# usb_shield.net
KiCad netlist of a schematic drawn in EAGLE
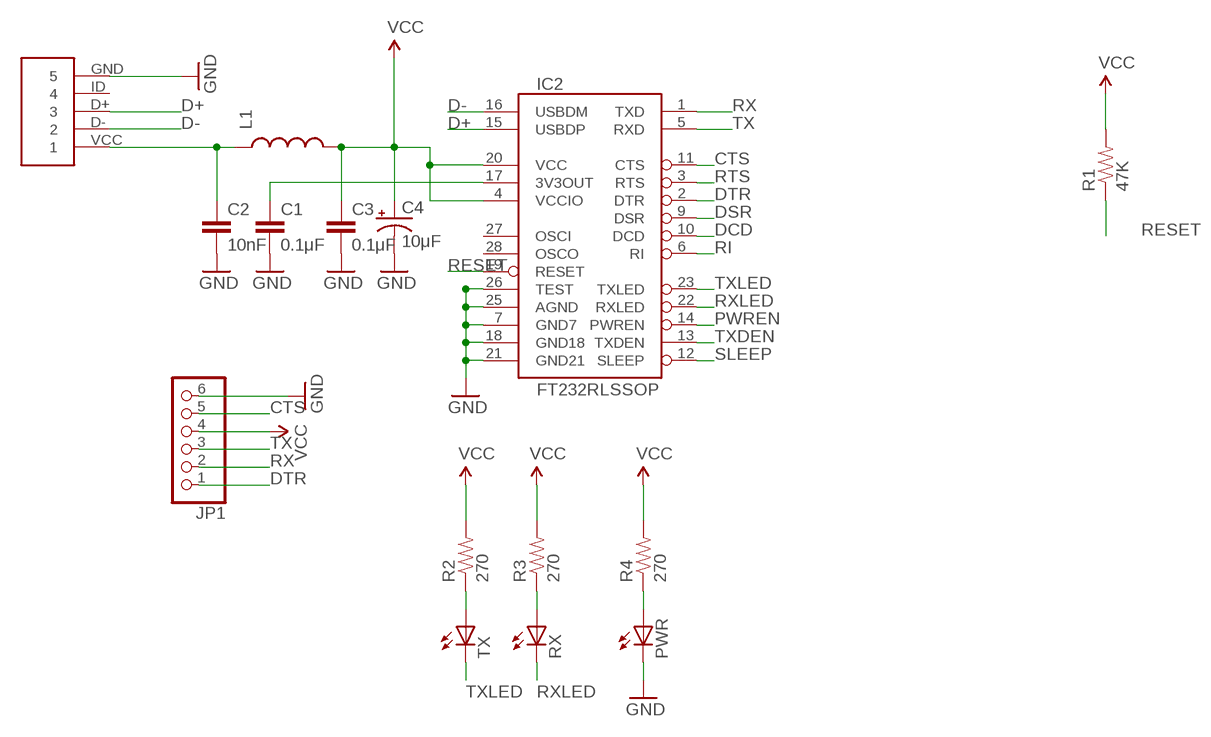
[diagram p0: schematic, sheet 1]

(export (version "E")
  (design (tool "Eeschema 10.0.6"))
  (components
    (comp (ref "C1")
      (value "0.1μF")
      (footprint "eagle-import:0603-CAP")
      (libsource (lib "eagle-import") (part "CAP0603-CAP"))
    )
    (comp (ref "C2")
      (value "10nF")
      (footprint "eagle-import:0603-CAP")
      (libsource (lib "eagle-import") (part "CAP0603-CAP"))
    )
    (comp (ref "C3")
      (value "0.1μF")
      (footprint "eagle-import:0603-CAP")
      (libsource (lib "eagle-import") (part "CAP0603-CAP"))
    )
    (comp (ref "C4")
      (value "10μF")
      (footprint "eagle-import:EIA3216")
      (libsource (lib "eagle-import") (part "CAP_POL1206"))
    )
    (comp (ref "IC2")
      (value "FT232RLSSOP")
      (footprint "eagle-import:SSOP28DB")
      (libsource (lib "eagle-import") (part "FT232RLSSOP"))
    )
    (comp (ref "JP1")
      (value "PINHD-1X6")
      (footprint "eagle-import:1X06")
      (libsource (lib "eagle-import") (part "PINHD-1X6"))
    )
    (comp (ref "L1")
      (value "INDUCTOR0603")
      (footprint "eagle-import:0603")
      (libsource (lib "eagle-import") (part "INDUCTOR0603"))
    )
    (comp (ref "PWR")
      (value "LEDCHIP-LED0805")
      (footprint "eagle-import:CHIP-LED0805")
      (libsource (lib "eagle-import") (part "LEDCHIP-LED0805"))
    )
    (comp (ref "R1")
      (value "47K")
      (footprint "eagle-import:0603-RES")
      (libsource (lib "eagle-import") (part "RESISTOR0603-RES"))
    )
    (comp (ref "R2")
      (value "270")
      (footprint "eagle-import:0603-RES")
      (libsource (lib "eagle-import") (part "RESISTOR0603-RES"))
    )
    (comp (ref "R3")
      (value "270")
      (footprint "eagle-import:0603-RES")
      (libsource (lib "eagle-import") (part "RESISTOR0603-RES"))
    )
    (comp (ref "R4")
      (value "270")
      (footprint "eagle-import:0603-RES")
      (libsource (lib "eagle-import") (part "RESISTOR0603-RES"))
    )
    (comp (ref "RX")
      (value "LEDCHIP-LED0805")
      (footprint "eagle-import:CHIP-LED0805")
      (libsource (lib "eagle-import") (part "LEDCHIP-LED0805"))
    )
    (comp (ref "TX")
      (value "LEDCHIP-LED0805")
      (footprint "eagle-import:CHIP-LED0805")
      (libsource (lib "eagle-import") (part "LEDCHIP-LED0805"))
    )
    (comp (ref "U$1")
      (value "USB-MICRO-B-FEMALE")
      (footprint "eagle-import:USB-MICRO-B-FEMALE")
      (libsource (lib "eagle-import") (part "USB-MICRO-B-FEMALE"))
    )
  )
  (nets
    (net (code "1") (name "/CTS") (class "Default")
      (node (ref "IC2") (pin "11") (pinfunction "CTS_11") (pintype "input"))
      (node (ref "JP1") (pin "5") (pinfunction "5_5") (pintype "passive"))
    )
    (net (code "2") (name "/D+") (class "Default")
      (node (ref "IC2") (pin "15") (pinfunction "USBDP_15") (pintype "bidirectional"))
      (node (ref "U$1") (pin "D+") (pinfunction "3_D+") (pintype "bidirectional"))
    )
    (net (code "3") (name "/D-") (class "Default")
      (node (ref "IC2") (pin "16") (pinfunction "USBDM_16") (pintype "bidirectional"))
      (node (ref "U$1") (pin "D-") (pinfunction "2_D-") (pintype "bidirectional"))
    )
    (net (code "4") (name "/DCD") (class "Default")
      (node (ref "IC2") (pin "10") (pinfunction "DCD_10") (pintype "input"))
    )
    (net (code "5") (name "/DSR") (class "Default")
      (node (ref "IC2") (pin "9") (pinfunction "DSR_9") (pintype "input"))
    )
    (net (code "6") (name "/DTR") (class "Default")
      (node (ref "IC2") (pin "2") (pinfunction "DTR_2") (pintype "output"))
      (node (ref "JP1") (pin "1") (pinfunction "1_1") (pintype "passive"))
    )
    (net (code "7") (name "/PWREN") (class "Default")
      (node (ref "IC2") (pin "14") (pinfunction "PWREN_14") (pintype "input"))
    )
    (net (code "8") (name "/RESET") (class "Default")
      (node (ref "IC2") (pin "19") (pinfunction "RESET_19") (pintype "input"))
      (node (ref "R1") (pin "1") (pinfunction "1_1") (pintype "passive"))
    )
    (net (code "9") (name "/RI") (class "Default")
      (node (ref "IC2") (pin "6") (pinfunction "RI_6") (pintype "input"))
    )
    (net (code "10") (name "/RTS") (class "Default")
      (node (ref "IC2") (pin "3") (pinfunction "RTS_3") (pintype "output"))
    )
    (net (code "11") (name "/RX") (class "Default")
      (node (ref "IC2") (pin "1") (pinfunction "TXD_1") (pintype "output"))
      (node (ref "JP1") (pin "2") (pinfunction "2_2") (pintype "passive"))
    )
    (net (code "12") (name "/RXLED") (class "Default")
      (node (ref "IC2") (pin "22") (pinfunction "RXLED_22") (pintype "input"))
      (node (ref "RX") (pin "C") (pinfunction "C_C") (pintype "passive"))
    )
    (net (code "13") (name "/SLEEP") (class "Default")
      (node (ref "IC2") (pin "12") (pinfunction "SLEEP_12") (pintype "input"))
    )
    (net (code "14") (name "/TX") (class "Default")
      (node (ref "IC2") (pin "5") (pinfunction "RXD_5") (pintype "input"))
      (node (ref "JP1") (pin "3") (pinfunction "3_3") (pintype "passive"))
    )
    (net (code "15") (name "/TXDEN") (class "Default")
      (node (ref "IC2") (pin "13") (pinfunction "TXDEN_13") (pintype "input"))
    )
    (net (code "16") (name "/TXLED") (class "Default")
      (node (ref "IC2") (pin "23") (pinfunction "TXLED_23") (pintype "input"))
      (node (ref "TX") (pin "C") (pinfunction "C_C") (pintype "passive"))
    )
    (net (code "17") (name "GND") (class "Default")
      (node (ref "C1") (pin "2") (pinfunction "2_2") (pintype "passive"))
      (node (ref "C2") (pin "2") (pinfunction "2_2") (pintype "passive"))
      (node (ref "C3") (pin "2") (pinfunction "2_2") (pintype "passive"))
      (node (ref "C4") (pin "C") (pinfunction "-_C") (pintype "passive"))
      (node (ref "IC2") (pin "18") (pinfunction "GND18_18") (pintype "power_in"))
      (node (ref "IC2") (pin "21") (pinfunction "GND21_21") (pintype "power_in"))
      (node (ref "IC2") (pin "25") (pinfunction "AGND_25") (pintype "power_in"))
      (node (ref "IC2") (pin "26") (pinfunction "TEST_26") (pintype "input"))
      (node (ref "IC2") (pin "7") (pinfunction "GND7_7") (pintype "power_in"))
      (node (ref "JP1") (pin "6") (pinfunction "6_6") (pintype "passive"))
      (node (ref "PWR") (pin "C") (pinfunction "C_C") (pintype "passive"))
      (node (ref "U$1") (pin "GND") (pinfunction "5_GND") (pintype "bidirectional"))
    )
    (net (code "18") (name "Net-(IC2-3V3OUT)") (class "Default")
      (node (ref "C1") (pin "1") (pinfunction "1_1") (pintype "passive"))
      (node (ref "IC2") (pin "17") (pinfunction "3V3OUT_17") (pintype "output"))
    )
    (net (code "19") (name "Net-(PWR-PadA)") (class "Default")
      (node (ref "PWR") (pin "A") (pinfunction "A_A") (pintype "passive"))
      (node (ref "R4") (pin "1") (pinfunction "1_1") (pintype "passive"))
    )
    (net (code "20") (name "Net-(R2-Pad1)") (class "Default")
      (node (ref "R2") (pin "1") (pinfunction "1_1") (pintype "passive"))
      (node (ref "TX") (pin "A") (pinfunction "A_A") (pintype "passive"))
    )
    (net (code "21") (name "Net-(R3-Pad1)") (class "Default")
      (node (ref "R3") (pin "1") (pinfunction "1_1") (pintype "passive"))
      (node (ref "RX") (pin "A") (pinfunction "A_A") (pintype "passive"))
    )
    (net (code "22") (name "Net-(U$1-1)") (class "Default")
      (node (ref "C2") (pin "1") (pinfunction "1_1") (pintype "passive"))
      (node (ref "L1") (pin "1") (pinfunction "1_1") (pintype "passive"))
      (node (ref "U$1") (pin "VCC") (pinfunction "1_VCC") (pintype "bidirectional"))
    )
    (net (code "23") (name "VCC") (class "Default")
      (node (ref "C3") (pin "1") (pinfunction "1_1") (pintype "passive"))
      (node (ref "C4") (pin "A") (pinfunction "+_A") (pintype "passive"))
      (node (ref "IC2") (pin "20") (pinfunction "VCC_20") (pintype "power_in"))
      (node (ref "IC2") (pin "4") (pinfunction "VCCIO_4") (pintype "power_in"))
      (node (ref "JP1") (pin "4") (pinfunction "4_4") (pintype "passive"))
      (node (ref "L1") (pin "2") (pinfunction "2_2") (pintype "passive"))
      (node (ref "R1") (pin "2") (pinfunction "2_2") (pintype "passive"))
      (node (ref "R2") (pin "2") (pinfunction "2_2") (pintype "passive"))
      (node (ref "R3") (pin "2") (pinfunction "2_2") (pintype "passive"))
      (node (ref "R4") (pin "2") (pinfunction "2_2") (pintype "passive"))
    )
    (net (code "24") (name "unconnected-(IC2-OSCI-Pad27)") (class "Default")
      (node (ref "IC2") (pin "27") (pinfunction "OSCI_27") (pintype "input"))
    )
    (net (code "25") (name "unconnected-(IC2-OSCO-Pad28)") (class "Default")
      (node (ref "IC2") (pin "28") (pinfunction "OSCO_28") (pintype "output"))
    )
    (net (code "26") (name "unconnected-(U$1-4-PadID)") (class "Default")
      (node (ref "U$1") (pin "ID") (pinfunction "4_ID") (pintype "bidirectional"))
    )
  )
)
